# Joy2PS2_rev2.net
KiCad netlist of a schematic drawn in EAGLE
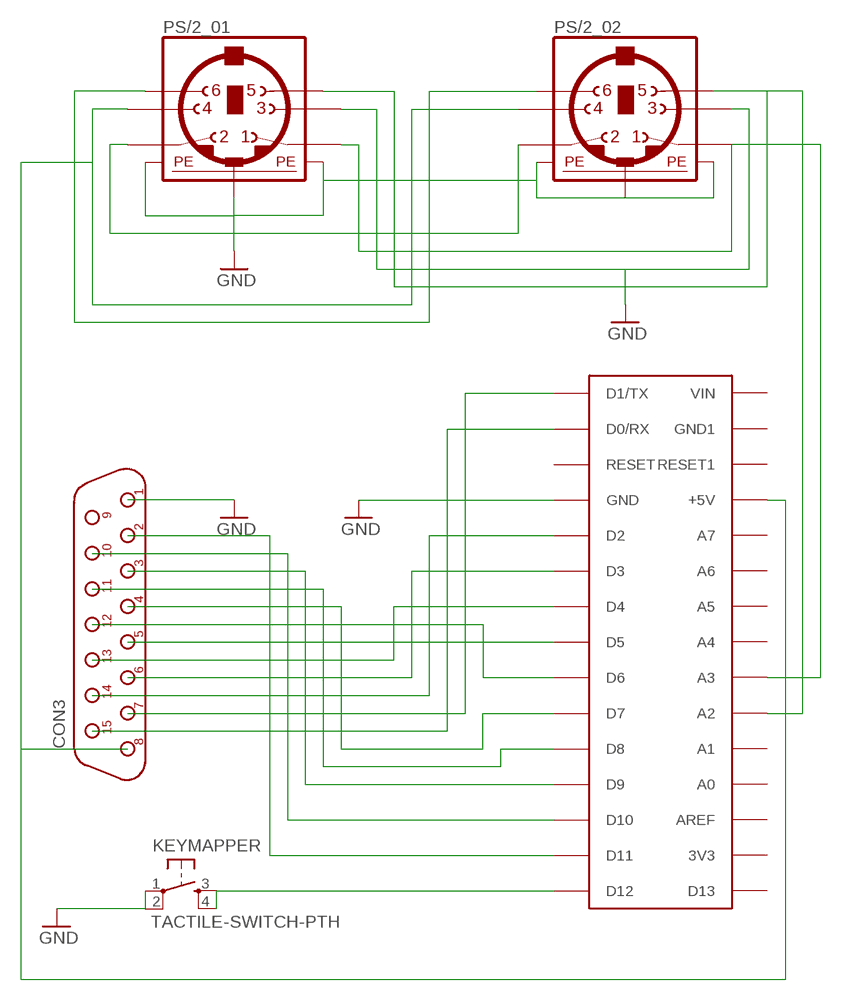
[diagram p0: schematic, sheet 1]

(export (version "E")
  (design (tool "Eeschema 10.0.6"))
  (components
    (comp (ref "ARDUINONANO")
      (value "ARDUINONANO")
      (footprint "eagle-import:PDIP-32")
      (libsource (lib "eagle-import") (part "ARDUINONANO"))
    )
    (comp (ref "CON3")
      (value "DB15M/90")
      (footprint "eagle-import:D-15M_90")
      (libsource (lib "eagle-import") (part "DB15M/90"))
    )
    (comp (ref "KEYMAPPER")
      (value "TACTILE-SWITCH-PTH")
      (footprint "eagle-import:TAC-SWITCH-PTH")
      (libsource (lib "eagle-import") (part "TACTILE-SWITCH-PTH"))
    )
    (comp (ref "PS/2_01")
      (value "MINI_DIN_6")
      (footprint "eagle-import:M_DIN6")
      (libsource (lib "eagle-import") (part "MINI_DIN_6"))
    )
    (comp (ref "PS/2_02")
      (value "MINI_DIN_6")
      (footprint "eagle-import:M_DIN6")
      (libsource (lib "eagle-import") (part "MINI_DIN_6"))
    )
  )
  (nets
    (net (code "1") (name "GND") (class "Default")
      (node (ref "ARDUINONANO") (pin "GND") (pinfunction "GND_GND") (pintype "bidirectional"))
      (node (ref "CON3") (pin "1") (pinfunction "1_1") (pintype "passive"))
      (node (ref "KEYMAPPER") (pin "1") (pinfunction "1_1") (pintype "passive"))
      (node (ref "KEYMAPPER") (pin "2") (pinfunction "2_2") (pintype "passive"))
      (node (ref "PS/2_01") (pin "3") (pinfunction "3_3") (pintype "passive"))
      (node (ref "PS/2_01") (pin "SH1") (pinfunction "PE1_SH1") (pintype "power_in"))
      (node (ref "PS/2_01") (pin "SH2") (pinfunction "PE2_SH2") (pintype "power_in"))
      (node (ref "PS/2_01") (pin "SH3") (pinfunction "PE3_SH3") (pintype "power_in"))
      (node (ref "PS/2_02") (pin "3") (pinfunction "3_3") (pintype "passive"))
      (node (ref "PS/2_02") (pin "SH1") (pinfunction "PE1_SH1") (pintype "power_in"))
      (node (ref "PS/2_02") (pin "SH2") (pinfunction "PE2_SH2") (pintype "power_in"))
      (node (ref "PS/2_02") (pin "SH3") (pinfunction "PE3_SH3") (pintype "power_in"))
    )
    (net (code "2") (name "Net-(ARDUINONANO-Pad+5V)") (class "Default")
      (node (ref "ARDUINONANO") (pin "+5V") (pinfunction "+5V_+5V") (pintype "bidirectional"))
      (node (ref "CON3") (pin "8") (pinfunction "8_8") (pintype "passive"))
      (node (ref "PS/2_01") (pin "4") (pinfunction "4_4") (pintype "passive"))
      (node (ref "PS/2_02") (pin "4") (pinfunction "4_4") (pintype "passive"))
    )
    (net (code "3") (name "Net-(ARDUINONANO-PadA2)") (class "Default")
      (node (ref "ARDUINONANO") (pin "A2") (pinfunction "A2_A2") (pintype "bidirectional"))
      (node (ref "PS/2_01") (pin "5") (pinfunction "5_5") (pintype "passive"))
      (node (ref "PS/2_02") (pin "5") (pinfunction "5_5") (pintype "passive"))
    )
    (net (code "4") (name "Net-(ARDUINONANO-PadA3)") (class "Default")
      (node (ref "ARDUINONANO") (pin "A3") (pinfunction "A3_A3") (pintype "bidirectional"))
      (node (ref "PS/2_01") (pin "1") (pinfunction "1_1") (pintype "passive"))
      (node (ref "PS/2_02") (pin "1") (pinfunction "1_1") (pintype "passive"))
    )
    (net (code "5") (name "Net-(ARDUINONANO-PadD0{slash}RX)") (class "Default")
      (node (ref "ARDUINONANO") (pin "D0/RX") (pinfunction "D0/RX_D0/RX") (pintype "bidirectional"))
      (node (ref "CON3") (pin "15") (pinfunction "15_15") (pintype "passive"))
    )
    (net (code "6") (name "Net-(ARDUINONANO-PadD1{slash}TX)") (class "Default")
      (node (ref "ARDUINONANO") (pin "D1/TX") (pinfunction "D1/TX_D1/TX") (pintype "bidirectional"))
      (node (ref "CON3") (pin "7") (pinfunction "7_7") (pintype "passive"))
    )
    (net (code "7") (name "Net-(ARDUINONANO-PadD2)") (class "Default")
      (node (ref "ARDUINONANO") (pin "D2") (pinfunction "D2_D2") (pintype "bidirectional"))
      (node (ref "CON3") (pin "14") (pinfunction "14_14") (pintype "passive"))
    )
    (net (code "8") (name "Net-(ARDUINONANO-PadD3)") (class "Default")
      (node (ref "ARDUINONANO") (pin "D3") (pinfunction "D3_D3") (pintype "bidirectional"))
      (node (ref "CON3") (pin "6") (pinfunction "6_6") (pintype "passive"))
    )
    (net (code "9") (name "Net-(ARDUINONANO-PadD4)") (class "Default")
      (node (ref "ARDUINONANO") (pin "D4") (pinfunction "D4_D4") (pintype "bidirectional"))
      (node (ref "CON3") (pin "13") (pinfunction "13_13") (pintype "passive"))
    )
    (net (code "10") (name "Net-(ARDUINONANO-PadD5)") (class "Default")
      (node (ref "ARDUINONANO") (pin "D5") (pinfunction "D5_D5") (pintype "bidirectional"))
      (node (ref "CON3") (pin "5") (pinfunction "5_5") (pintype "passive"))
    )
    (net (code "11") (name "Net-(ARDUINONANO-PadD6)") (class "Default")
      (node (ref "ARDUINONANO") (pin "D6") (pinfunction "D6_D6") (pintype "bidirectional"))
      (node (ref "CON3") (pin "12") (pinfunction "12_12") (pintype "passive"))
    )
    (net (code "12") (name "Net-(ARDUINONANO-PadD7)") (class "Default")
      (node (ref "ARDUINONANO") (pin "D7") (pinfunction "D7_D7") (pintype "bidirectional"))
      (node (ref "CON3") (pin "4") (pinfunction "4_4") (pintype "passive"))
    )
    (net (code "13") (name "Net-(ARDUINONANO-PadD8)") (class "Default")
      (node (ref "ARDUINONANO") (pin "D8") (pinfunction "D8_D8") (pintype "bidirectional"))
      (node (ref "CON3") (pin "11") (pinfunction "11_11") (pintype "passive"))
    )
    (net (code "14") (name "Net-(ARDUINONANO-PadD9)") (class "Default")
      (node (ref "ARDUINONANO") (pin "D9") (pinfunction "D9_D9") (pintype "bidirectional"))
      (node (ref "CON3") (pin "3") (pinfunction "3_3") (pintype "passive"))
    )
    (net (code "15") (name "Net-(ARDUINONANO-PadD10)") (class "Default")
      (node (ref "ARDUINONANO") (pin "D10") (pinfunction "D10_D10") (pintype "bidirectional"))
      (node (ref "CON3") (pin "10") (pinfunction "10_10") (pintype "passive"))
    )
    (net (code "16") (name "Net-(ARDUINONANO-PadD11)") (class "Default")
      (node (ref "ARDUINONANO") (pin "D11") (pinfunction "D11_D11") (pintype "bidirectional"))
      (node (ref "CON3") (pin "2") (pinfunction "2_2") (pintype "passive"))
    )
    (net (code "17") (name "Net-(ARDUINONANO-PadD12)") (class "Default")
      (node (ref "ARDUINONANO") (pin "D12") (pinfunction "D12_D12") (pintype "bidirectional"))
      (node (ref "KEYMAPPER") (pin "3") (pinfunction "3_3") (pintype "passive"))
      (node (ref "KEYMAPPER") (pin "4") (pinfunction "4_4") (pintype "passive"))
    )
    (net (code "18") (name "Net-(PS/2_01-Pad2)") (class "Default")
      (node (ref "PS/2_01") (pin "2") (pinfunction "2_2") (pintype "passive"))
      (node (ref "PS/2_02") (pin "2") (pinfunction "2_2") (pintype "passive"))
    )
    (net (code "19") (name "Net-(PS/2_01-Pad6)") (class "Default")
      (node (ref "PS/2_01") (pin "6") (pinfunction "6_6") (pintype "passive"))
      (node (ref "PS/2_02") (pin "6") (pinfunction "6_6") (pintype "passive"))
    )
    (net (code "20") (name "unconnected-(ARDUINONANO-Pad3V3)") (class "Default")
      (node (ref "ARDUINONANO") (pin "3V3") (pinfunction "3V3_3V3") (pintype "bidirectional"))
    )
    (net (code "21") (name "unconnected-(ARDUINONANO-PadA0)") (class "Default")
      (node (ref "ARDUINONANO") (pin "A0") (pinfunction "A0_A0") (pintype "bidirectional"))
    )
    (net (code "22") (name "unconnected-(ARDUINONANO-PadA1)") (class "Default")
      (node (ref "ARDUINONANO") (pin "A1") (pinfunction "A1_A1") (pintype "bidirectional"))
    )
    (net (code "23") (name "unconnected-(ARDUINONANO-PadA4)") (class "Default")
      (node (ref "ARDUINONANO") (pin "A4") (pinfunction "A4_A4") (pintype "bidirectional"))
    )
    (net (code "24") (name "unconnected-(ARDUINONANO-PadA5)") (class "Default")
      (node (ref "ARDUINONANO") (pin "A5") (pinfunction "A5_A5") (pintype "bidirectional"))
    )
    (net (code "25") (name "unconnected-(ARDUINONANO-PadA6)") (class "Default")
      (node (ref "ARDUINONANO") (pin "A6") (pinfunction "A6_A6") (pintype "bidirectional"))
    )
    (net (code "26") (name "unconnected-(ARDUINONANO-PadA7)") (class "Default")
      (node (ref "ARDUINONANO") (pin "A7") (pinfunction "A7_A7") (pintype "bidirectional"))
    )
    (net (code "27") (name "unconnected-(ARDUINONANO-PadAREF)") (class "Default")
      (node (ref "ARDUINONANO") (pin "AREF") (pinfunction "AREF_AREF") (pintype "bidirectional"))
    )
    (net (code "28") (name "unconnected-(ARDUINONANO-PadD13)") (class "Default")
      (node (ref "ARDUINONANO") (pin "D13") (pinfunction "D13_D13") (pintype "bidirectional"))
    )
    (net (code "29") (name "unconnected-(ARDUINONANO-PadGND1)") (class "Default")
      (node (ref "ARDUINONANO") (pin "GND1") (pinfunction "GND1_GND1") (pintype "bidirectional"))
    )
    (net (code "30") (name "unconnected-(ARDUINONANO-PadRESET)") (class "Default")
      (node (ref "ARDUINONANO") (pin "RESET") (pinfunction "RESET_RESET") (pintype "bidirectional"))
    )
    (net (code "31") (name "unconnected-(ARDUINONANO-PadRESET1)") (class "Default")
      (node (ref "ARDUINONANO") (pin "RESET1") (pinfunction "RESET1_RESET1") (pintype "bidirectional"))
    )
    (net (code "32") (name "unconnected-(ARDUINONANO-PadVIN)") (class "Default")
      (node (ref "ARDUINONANO") (pin "VIN") (pinfunction "VIN_VIN") (pintype "bidirectional"))
    )
    (net (code "33") (name "unconnected-(CON3-Pad9)") (class "Default")
      (node (ref "CON3") (pin "9") (pinfunction "9_9") (pintype "passive"))
    )
  )
)
